# ArduinoProMiniSch.net
KiCad netlist of a schematic drawn in Altium Designer
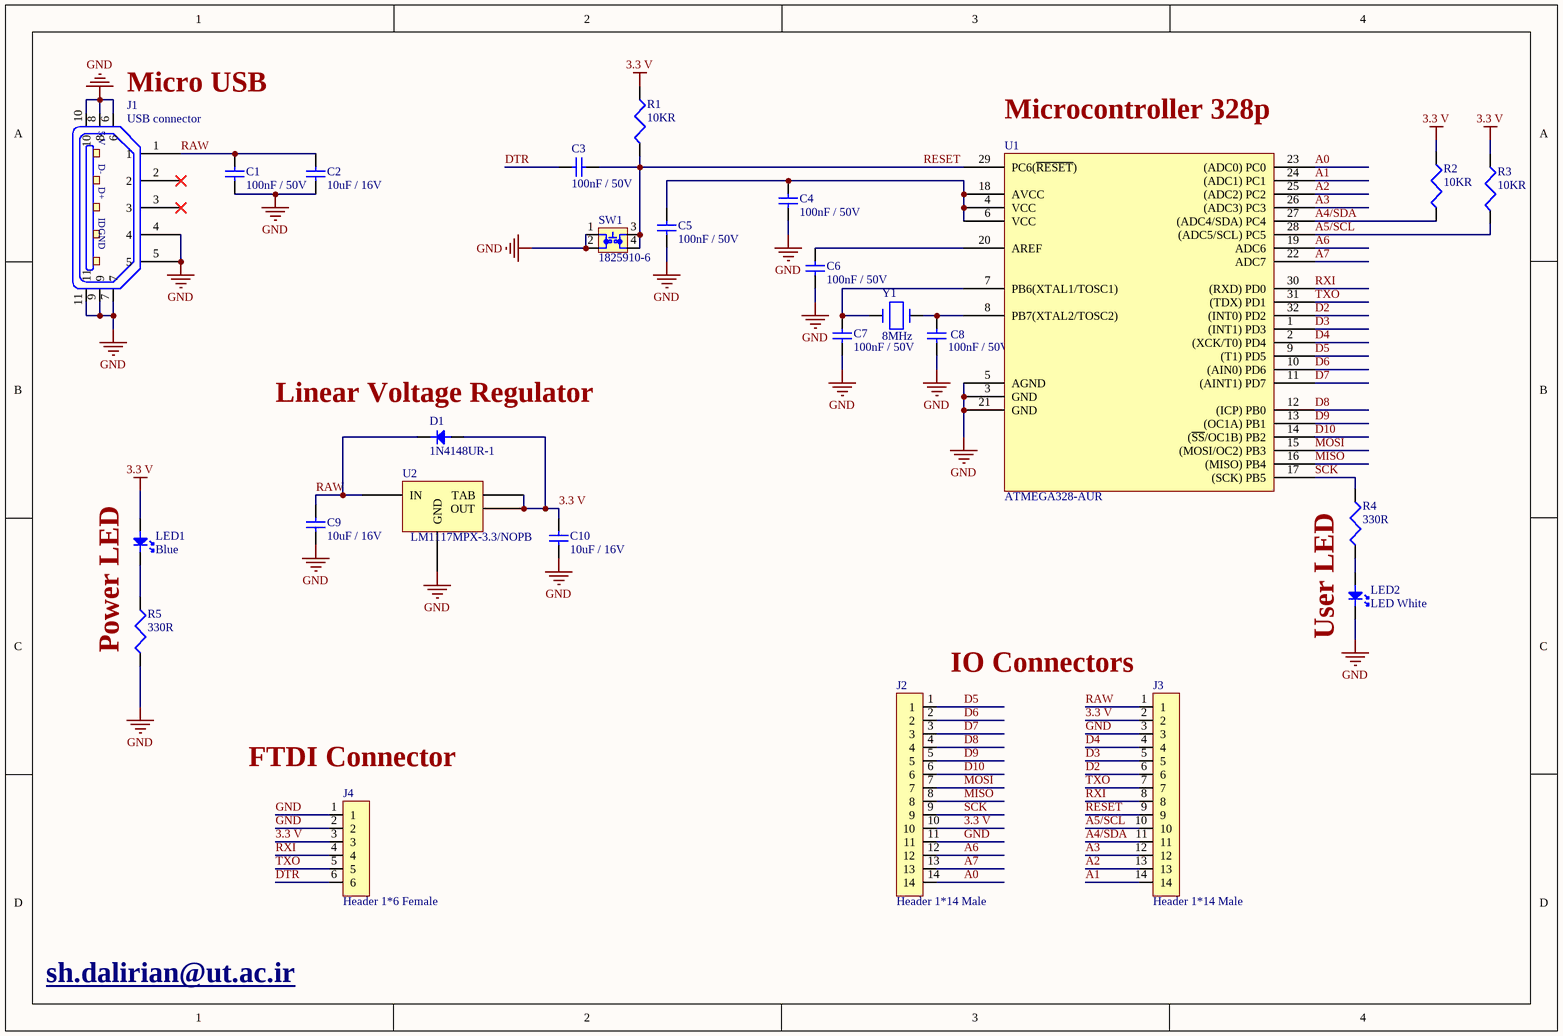
[diagram p0: ArduinoProMiniSch.SchDoc]

(export (version "E")
  (design (tool "Eeschema 10.0.6"))
  (components
    (comp (ref "C1")
      (value "100nF / 50V")
      (footprint "C 0805")
      (description "Capacitor; Ceramic; Cap; .100uF; Tol%; -20%; SMT; Vol-Rtg 50V; Y5V; TR ¦ KEMET C0805C104Z5VACTU")
      (fields
        (field (name "MANUFACTURER") "KEMET")
        (field (name "MANUFACTURER PART NUMBER") "C0805C104Z5VACTU")
      )
      (libsource (lib "ArduinoProMiniSchLib") (part "C0805C104Z5VACTU"))
    )
    (comp (ref "C2")
      (value "10uF / 16V")
      (footprint "C 0805")
      (description "Ceramic capacitor, 10 µF, 16 V (DC), ±10 %, SMD 0805, X5R, C0805C106K4PAC7800")
      (fields
        (field (name "MANUFACTURER") "KEMET")
        (field (name "MANUFACTURER PART NUMBER") "C0805C106K4PACTU")
      )
      (libsource (lib "ArduinoProMiniSchLib") (part "C0805C106K4PACTU"))
    )
    (comp (ref "C3")
      (value "100nF / 50V")
      (footprint "C 0805")
      (description "Capacitor; Ceramic; Cap; .100uF; Tol%; -20%; SMT; Vol-Rtg 50V; Y5V; TR ¦ KEMET C0805C104Z5VACTU")
      (fields
        (field (name "MANUFACTURER") "KEMET")
        (field (name "MANUFACTURER PART NUMBER") "C0805C104Z5VACTU")
      )
      (libsource (lib "ArduinoProMiniSchLib") (part "C0805C104Z5VACTU"))
    )
    (comp (ref "C4")
      (value "100nF / 50V")
      (footprint "C 0805")
      (description "Capacitor; Ceramic; Cap; .100uF; Tol%; -20%; SMT; Vol-Rtg 50V; Y5V; TR ¦ KEMET C0805C104Z5VACTU")
      (fields
        (field (name "MANUFACTURER") "KEMET")
        (field (name "MANUFACTURER PART NUMBER") "C0805C104Z5VACTU")
      )
      (libsource (lib "ArduinoProMiniSchLib") (part "C0805C104Z5VACTU"))
    )
    (comp (ref "C5")
      (value "100nF / 50V")
      (footprint "C 0805")
      (description "Capacitor; Ceramic; Cap; .100uF; Tol%; -20%; SMT; Vol-Rtg 50V; Y5V; TR ¦ KEMET C0805C104Z5VACTU")
      (fields
        (field (name "MANUFACTURER") "KEMET")
        (field (name "MANUFACTURER PART NUMBER") "C0805C104Z5VACTU")
      )
      (libsource (lib "ArduinoProMiniSchLib") (part "C0805C104Z5VACTU"))
    )
    (comp (ref "C6")
      (value "100nF / 50V")
      (footprint "C 0805")
      (description "Capacitor; Ceramic; Cap; .100uF; Tol%; -20%; SMT; Vol-Rtg 50V; Y5V; TR ¦ KEMET C0805C104Z5VACTU")
      (fields
        (field (name "MANUFACTURER") "KEMET")
        (field (name "MANUFACTURER PART NUMBER") "C0805C104Z5VACTU")
      )
      (libsource (lib "ArduinoProMiniSchLib") (part "C0805C104Z5VACTU"))
    )
    (comp (ref "C7")
      (value "100nF / 50V")
      (footprint "C 0805")
      (description "Capacitor; Ceramic; Cap; .100uF; Tol%; -20%; SMT; Vol-Rtg 50V; Y5V; TR ¦ KEMET C0805C104Z5VACTU")
      (fields
        (field (name "MANUFACTURER") "KEMET")
        (field (name "MANUFACTURER PART NUMBER") "C0805C104Z5VACTU")
      )
      (libsource (lib "ArduinoProMiniSchLib") (part "C0805C104Z5VACTU"))
    )
    (comp (ref "C8")
      (value "100nF / 50V")
      (footprint "C 0805")
      (description "Capacitor; Ceramic; Cap; .100uF; Tol%; -20%; SMT; Vol-Rtg 50V; Y5V; TR ¦ KEMET C0805C104Z5VACTU")
      (fields
        (field (name "MANUFACTURER") "KEMET")
        (field (name "MANUFACTURER PART NUMBER") "C0805C104Z5VACTU")
      )
      (libsource (lib "ArduinoProMiniSchLib") (part "C0805C104Z5VACTU"))
    )
    (comp (ref "C9")
      (value "10uF / 16V")
      (footprint "C 0805")
      (description "Ceramic capacitor, 10 µF, 16 V (DC), ±10 %, SMD 0805, X5R, C0805C106K4PAC7800")
      (fields
        (field (name "MANUFACTURER") "KEMET")
        (field (name "MANUFACTURER PART NUMBER") "C0805C106K4PACTU")
      )
      (libsource (lib "ArduinoProMiniSchLib") (part "C0805C106K4PACTU"))
    )
    (comp (ref "C10")
      (value "10uF / 16V")
      (footprint "C 0805")
      (description "Ceramic capacitor, 10 µF, 16 V (DC), ±10 %, SMD 0805, X5R, C0805C106K4PAC7800")
      (fields
        (field (name "MANUFACTURER") "KEMET")
        (field (name "MANUFACTURER PART NUMBER") "C0805C106K4PACTU")
      )
      (libsource (lib "ArduinoProMiniSchLib") (part "C0805C106K4PACTU"))
    )
    (comp (ref "D1")
      (value "1N4148UR-1")
      (footprint "DO-213AA")
      (description "Rectifier Diode Switching 75V 0.2A 5ns 2-Pin DO-213AA Bag")
      (fields (field (name "MANUFACTURER") "Microchip"))
      (libsource (lib "ArduinoProMiniSchLib") (part "1N4148UR-1"))
    )
    (comp (ref "J1")
      (value "USB connector")
      (footprint "USB connector")
      (description "CONN USB MICRO B RECPT SMT R/A")
      (fields
        (field (name "MANUFACTURER") "Amphenol ICC / FCI")
        (field (name "MANUFACTURER PART NUMBER") "10118194-0001LF")
      )
      (libsource (lib "ArduinoProMiniSchLib") (part "10118194-0001LF"))
    )
    (comp (ref "J2")
      (value "Header 1*14 Male")
      (footprint "Header 1*14 Male")
      (description "Conn Unshrouded Header HDR 14 POS 2.54mm Solder ST Thru-Hole Bag")
      (fields
        (field (name "MANUFACTURER") "Adam Equipment")
        (field (name "MANUFACTURER PART NUMBER") "PH1-14-UA")
      )
      (libsource (lib "ArduinoProMiniSchLib") (part "PH1-14-UA"))
    )
    (comp (ref "J3")
      (value "Header 1*14 Male")
      (footprint "Header 1*14 Male")
      (description "Conn Unshrouded Header HDR 14 POS 2.54mm Solder ST Thru-Hole Bag")
      (fields
        (field (name "MANUFACTURER") "Adam Equipment")
        (field (name "MANUFACTURER PART NUMBER") "PH1-14-UA")
      )
      (libsource (lib "") (part "PH1-14-UA_1"))
    )
    (comp (ref "J4")
      (value "Header 1*6 Female")
      (footprint "Header 1*6 Female")
      (description "2.54mm (0.1\") Pitch SIL Vertical PC Tail Socket Assembly, tin, 6 contacts")
      (fields (field (name "MANUFACTURER") "Harwin") (field (name "MANUFACTURER PART NUMBER") "M20-7820646"))
      (libsource (lib "ArduinoProMiniSchLib") (part "M20-7820646"))
    )
    (comp (ref "LED1")
      (value "Blue")
      (footprint "LED 0603")
      (description "LED BLUE CLEAR 0603 SMD")
      (fields
        (field (name "MANUFACTURER") "Vishay Lite-On")
        (field (name "MANUFACTURER PART NUMBER") "LTST-C194TBKT")
      )
      (libsource (lib "ArduinoProMiniSchLib") (part "LTST-C194TBKT"))
    )
    (comp (ref "LED2")
      (value "LED White")
      (footprint "LED 0603")
      (fields (field (name "MANUFACTURER") "Inolux") (field (name "MANUFACTURER PART NUMBER") "IN-S63AT5UW"))
      (libsource (lib "ArduinoProMiniSchLib") (part "IN-S63AT5UW"))
    )
    (comp (ref "R1")
      (value "10KR")
      (footprint "R 0805")
      (description "Res Thick Film 0805 10K Ohm 1% 0.125W(1/8W) +/-100ppm/C Epoxy Pad SMD T/R")
      (fields
        (field (name "MANUFACTURER") "Yageo")
        (field (name "MANUFACTURER PART NUMBER") "RC0805FR-0710KL")
      )
      (libsource (lib "ArduinoProMiniSchLib") (part "RC0805FR-0710KL"))
    )
    (comp (ref "R2")
      (value "10KR")
      (footprint "R 0805")
      (description "Res Thick Film 0805 10K Ohm 1% 0.125W(1/8W) +/-100ppm/C Epoxy Pad SMD T/R")
      (fields
        (field (name "MANUFACTURER") "Yageo")
        (field (name "MANUFACTURER PART NUMBER") "RC0805FR-0710KL")
      )
      (libsource (lib "ArduinoProMiniSchLib") (part "RC0805FR-0710KL"))
    )
    (comp (ref "R3")
      (value "10KR")
      (footprint "R 0805")
      (description "Res Thick Film 0805 10K Ohm 1% 0.125W(1/8W) +/-100ppm/C Epoxy Pad SMD T/R")
      (fields
        (field (name "MANUFACTURER") "Yageo")
        (field (name "MANUFACTURER PART NUMBER") "RC0805FR-0710KL")
      )
      (libsource (lib "ArduinoProMiniSchLib") (part "RC0805FR-0710KL"))
    )
    (comp (ref "R4")
      (value "330R")
      (footprint "R 0805")
      (description "SMD Chip Resistor 330 Ohm ½ 5% 125 Mw 0805 [2012 Metric] Thick Film General Purpose")
      (fields
        (field (name "MANUFACTURER") "Yageo")
        (field (name "MANUFACTURER PART NUMBER") "RC0805JR-07330RL")
      )
      (libsource (lib "ArduinoProMiniSchLib") (part "RC0805JR-07330RL"))
    )
    (comp (ref "R5")
      (value "330R")
      (footprint "R 0805")
      (description "SMD Chip Resistor 330 Ohm ½ 5% 125 Mw 0805 [2012 Metric] Thick Film General Purpose")
      (fields
        (field (name "MANUFACTURER") "Yageo")
        (field (name "MANUFACTURER PART NUMBER") "RC0805JR-07330RL")
      )
      (libsource (lib "ArduinoProMiniSchLib") (part "RC0805JR-07330RL"))
    )
    (comp (ref "SW1")
      (value "1825910-6")
      (footprint "SW-1825910-6")
      (description "Switch Tactile OFF (ON) SPST Round Button PC Pins 0.05A 24VDC 1.57N Thru-Hole Loose")
      (fields (field (name "MANUFACTURER") "TE Connectivity Alcoswitch"))
      (libsource (lib "ArduinoProMiniSchLib") (part "1825910-6"))
    )
    (comp (ref "U1")
      (value "ATMEGA328-AUR")
      (footprint "TQFP32")
      (description "MCU 8-bit ATmega AVR RISC 32KB Flash 2.5V/3.3V/5V 32-Pin TQFP T/R - Tape and Reel")
      (fields (field (name "MANUFACTURER") "Microchip"))
      (libsource (lib "ArduinoProMiniSchLib") (part "ATMEGA328-AUR"))
    )
    (comp (ref "U2")
      (value "LM1117MPX-3.3/NOPB")
      (footprint "SOT223")
      (description "800-mA 15-V linear voltage regulator ; 4-SOT-223 0 to 125")
      (fields (field (name "MANUFACTURER") "Texas Instruments"))
      (libsource (lib "ArduinoProMiniSchLib") (part "LM1117MPX-3.3/NOPB"))
    )
    (comp (ref "Y1")
      (value "8MHz")
      (footprint "CSM-7x")
      (description "Crystal 8MHz ±30ppm (Tol) ±50ppm (Stability) 18pF FUND 60Ohm 2-Pin HC-49/USX SMD T/R")
      (fields
        (field (name "MANUFACTURER") "ECS International")
        (field (name "MANUFACTURER PART NUMBER") "ECS-80-18-5PX-TR")
      )
      (libsource (lib "ArduinoProMiniSchLib") (part "ECS-80-18-5PX-TR"))
    )
  )
  (nets
    (net (code "1") (name "/A0") (class "Default")
      (node (ref "J2") (pin "14") (pinfunction "14_14") (pintype "passive"))
      (node (ref "U1") (pin "23") (pinfunction "(ADC0)_PC0_23") (pintype "passive"))
    )
    (net (code "2") (name "/A1") (class "Default")
      (node (ref "J3") (pin "14") (pinfunction "14_14") (pintype "passive"))
      (node (ref "U1") (pin "24") (pinfunction "(ADC1)_PC1_24") (pintype "passive"))
    )
    (net (code "3") (name "/A2") (class "Default")
      (node (ref "J3") (pin "13") (pinfunction "13_13") (pintype "passive"))
      (node (ref "U1") (pin "25") (pinfunction "(ADC2)_PC2_25") (pintype "passive"))
    )
    (net (code "4") (name "/A3") (class "Default")
      (node (ref "J3") (pin "12") (pinfunction "12_12") (pintype "passive"))
      (node (ref "U1") (pin "26") (pinfunction "(ADC3)_PC3_26") (pintype "passive"))
    )
    (net (code "5") (name "/A4{slash}SDA") (class "Default")
      (node (ref "J3") (pin "11") (pinfunction "11_11") (pintype "passive"))
      (node (ref "R2") (pin "1") (pinfunction "1_1") (pintype "passive"))
      (node (ref "U1") (pin "27") (pinfunction "(ADC4/SDA)_PC4_27") (pintype "passive"))
    )
    (net (code "6") (name "/A5{slash}SCL") (class "Default")
      (node (ref "J3") (pin "10") (pinfunction "10_10") (pintype "passive"))
      (node (ref "R3") (pin "1") (pinfunction "1_1") (pintype "passive"))
      (node (ref "U1") (pin "28") (pinfunction "(ADC5/SCL)_PC5_28") (pintype "passive"))
    )
    (net (code "7") (name "/A6") (class "Default")
      (node (ref "J2") (pin "12") (pinfunction "12_12") (pintype "passive"))
      (node (ref "U1") (pin "19") (pinfunction "ADC6_19") (pintype "passive"))
    )
    (net (code "8") (name "/A7") (class "Default")
      (node (ref "J2") (pin "13") (pinfunction "13_13") (pintype "passive"))
      (node (ref "U1") (pin "22") (pinfunction "ADC7_22") (pintype "passive"))
    )
    (net (code "9") (name "/D2") (class "Default")
      (node (ref "J3") (pin "6") (pinfunction "6_6") (pintype "passive"))
      (node (ref "U1") (pin "32") (pinfunction "(INT0)_PD2_32") (pintype "passive"))
    )
    (net (code "10") (name "/D3") (class "Default")
      (node (ref "J3") (pin "5") (pinfunction "5_5") (pintype "passive"))
      (node (ref "U1") (pin "1") (pinfunction "(INT1)_PD3_1") (pintype "passive"))
    )
    (net (code "11") (name "/D4") (class "Default")
      (node (ref "J3") (pin "4") (pinfunction "4_4") (pintype "passive"))
      (node (ref "U1") (pin "2") (pinfunction "(XCK/T0)_PD4_2") (pintype "passive"))
    )
    (net (code "12") (name "/D5") (class "Default")
      (node (ref "J2") (pin "1") (pinfunction "1_1") (pintype "passive"))
      (node (ref "U1") (pin "9") (pinfunction "(T1)_PD5_9") (pintype "passive"))
    )
    (net (code "13") (name "/D6") (class "Default")
      (node (ref "J2") (pin "2") (pinfunction "2_2") (pintype "passive"))
      (node (ref "U1") (pin "10") (pinfunction "(AIN0)_PD6_10") (pintype "passive"))
    )
    (net (code "14") (name "/D7") (class "Default")
      (node (ref "J2") (pin "3") (pinfunction "3_3") (pintype "passive"))
      (node (ref "U1") (pin "11") (pinfunction "(AINT1)_PD7_11") (pintype "passive"))
    )
    (net (code "15") (name "/D8") (class "Default")
      (node (ref "J2") (pin "4") (pinfunction "4_4") (pintype "passive"))
      (node (ref "U1") (pin "12") (pinfunction "(ICP)_PB0_12") (pintype "passive"))
    )
    (net (code "16") (name "/D9") (class "Default")
      (node (ref "J2") (pin "5") (pinfunction "5_5") (pintype "passive"))
      (node (ref "U1") (pin "13") (pinfunction "(OC1A)_PB1_13") (pintype "passive"))
    )
    (net (code "17") (name "/D10") (class "Default")
      (node (ref "J2") (pin "6") (pinfunction "6_6") (pintype "passive"))
      (node (ref "U1") (pin "14") (pinfunction "(~{SS}/OC1B)_PB2_14") (pintype "passive"))
    )
    (net (code "18") (name "/DTR") (class "Default")
      (node (ref "C3") (pin "1") (pinfunction "1_1") (pintype "passive"))
      (node (ref "J4") (pin "6") (pinfunction "6_6") (pintype "passive"))
    )
    (net (code "19") (name "/MISO") (class "Default")
      (node (ref "J2") (pin "8") (pinfunction "8_8") (pintype "passive"))
      (node (ref "U1") (pin "16") (pinfunction "(MISO)_PB4_16") (pintype "passive"))
    )
    (net (code "20") (name "/MOSI") (class "Default")
      (node (ref "J2") (pin "7") (pinfunction "7_7") (pintype "passive"))
      (node (ref "U1") (pin "15") (pinfunction "(MOSI/OC2)_PB3_15") (pintype "passive"))
    )
    (net (code "21") (name "/RAW") (class "Default")
      (node (ref "C1") (pin "2") (pinfunction "2_2") (pintype "passive"))
      (node (ref "C2") (pin "2") (pinfunction "2_2") (pintype "passive"))
      (node (ref "C9") (pin "2") (pinfunction "2_2") (pintype "passive"))
      (node (ref "D1") (pin "2") (pinfunction "Cathode_2") (pintype "passive"))
      (node (ref "J1") (pin "1") (pinfunction "1_1") (pintype "passive"))
      (node (ref "J3") (pin "1") (pinfunction "1_1") (pintype "passive"))
      (node (ref "U2") (pin "4") (pinfunction "IN_4") (pintype "passive"))
    )
    (net (code "22") (name "/RESET") (class "Default")
      (node (ref "C3") (pin "2") (pinfunction "2_2") (pintype "passive"))
      (node (ref "J3") (pin "9") (pinfunction "9_9") (pintype "passive"))
      (node (ref "R1") (pin "1") (pinfunction "1_1") (pintype "passive"))
      (node (ref "SW1") (pin "3") (pinfunction "3_3") (pintype "passive"))
      (node (ref "SW1") (pin "4") (pinfunction "4_4") (pintype "passive"))
      (node (ref "U1") (pin "29") (pinfunction "PC6(~{RESET})_29") (pintype "passive"))
    )
    (net (code "23") (name "/RXI") (class "Default")
      (node (ref "J3") (pin "8") (pinfunction "8_8") (pintype "passive"))
      (node (ref "J4") (pin "4") (pinfunction "4_4") (pintype "passive"))
      (node (ref "U1") (pin "30") (pinfunction "(RXD)_PD0_30") (pintype "passive"))
    )
    (net (code "24") (name "/SCK") (class "Default")
      (node (ref "J2") (pin "9") (pinfunction "9_9") (pintype "passive"))
      (node (ref "R4") (pin "2") (pinfunction "2_2") (pintype "passive"))
      (node (ref "U1") (pin "17") (pinfunction "(SCK)_PB5_17") (pintype "passive"))
    )
    (net (code "25") (name "/TXO") (class "Default")
      (node (ref "J3") (pin "7") (pinfunction "7_7") (pintype "passive"))
      (node (ref "J4") (pin "5") (pinfunction "5_5") (pintype "passive"))
      (node (ref "U1") (pin "31") (pinfunction "(TDX)_PD1_31") (pintype "passive"))
    )
    (net (code "26") (name "3.3 V") (class "Default")
      (node (ref "C10") (pin "2") (pinfunction "2_2") (pintype "passive"))
      (node (ref "D1") (pin "1") (pinfunction "Anode_1") (pintype "passive"))
      (node (ref "J2") (pin "10") (pinfunction "10_10") (pintype "passive"))
      (node (ref "J3") (pin "2") (pinfunction "2_2") (pintype "passive"))
      (node (ref "J4") (pin "3") (pinfunction "3_3") (pintype "passive"))
      (node (ref "LED1") (pin "1") (pinfunction "Anode_1") (pintype "passive"))
      (node (ref "R1") (pin "2") (pinfunction "2_2") (pintype "passive"))
      (node (ref "R2") (pin "2") (pinfunction "2_2") (pintype "passive"))
      (node (ref "R3") (pin "2") (pinfunction "2_2") (pintype "passive"))
      (node (ref "U2") (pin "2") (pinfunction "OUT_2") (pintype "passive"))
      (node (ref "U2") (pin "3") (pinfunction "TAB_3") (pintype "passive"))
    )
    (net (code "27") (name "GND") (class "Default")
      (node (ref "C1") (pin "1") (pinfunction "1_1") (pintype "passive"))
      (node (ref "C10") (pin "1") (pinfunction "1_1") (pintype "passive"))
      (node (ref "C2") (pin "1") (pinfunction "1_1") (pintype "passive"))
      (node (ref "C4") (pin "1") (pinfunction "1_1") (pintype "passive"))
      (node (ref "C5") (pin "1") (pinfunction "1_1") (pintype "passive"))
      (node (ref "C6") (pin "1") (pinfunction "1_1") (pintype "passive"))
      (node (ref "C7") (pin "1") (pinfunction "1_1") (pintype "passive"))
      (node (ref "C8") (pin "1") (pinfunction "1_1") (pintype "passive"))
      (node (ref "C9") (pin "1") (pinfunction "1_1") (pintype "passive"))
      (node (ref "J1") (pin "10") (pinfunction "10_10") (pintype "passive"))
      (node (ref "J1") (pin "11") (pinfunction "11_11") (pintype "passive"))
      (node (ref "J1") (pin "4") (pinfunction "4_4") (pintype "passive"))
      (node (ref "J1") (pin "5") (pinfunction "5_5") (pintype "passive"))
      (node (ref "J1") (pin "6") (pinfunction "6_6") (pintype "passive"))
      (node (ref "J1") (pin "7") (pinfunction "7_7") (pintype "passive"))
      (node (ref "J1") (pin "8") (pinfunction "8_8") (pintype "passive"))
      (node (ref "J1") (pin "9") (pinfunction "9_9") (pintype "passive"))
      (node (ref "J2") (pin "11") (pinfunction "11_11") (pintype "passive"))
      (node (ref "J3") (pin "3") (pinfunction "3_3") (pintype "passive"))
      (node (ref "J4") (pin "1") (pinfunction "1_1") (pintype "passive"))
      (node (ref "J4") (pin "2") (pinfunction "2_2") (pintype "passive"))
      (node (ref "LED2") (pin "2") (pinfunction "Cathode_2") (pintype "passive"))
      (node (ref "R5") (pin "1") (pinfunction "1_1") (pintype "passive"))
      (node (ref "SW1") (pin "1") (pinfunction "3_1") (pintype "passive"))
      (node (ref "SW1") (pin "2") (pinfunction "2_2") (pintype "passive"))
      (node (ref "U1") (pin "21") (pinfunction "GND_21") (pintype "passive"))
      (node (ref "U1") (pin "3") (pinfunction "GND_3") (pintype "passive"))
      (node (ref "U1") (pin "5") (pinfunction "AGND_5") (pintype "passive"))
      (node (ref "U2") (pin "1") (pinfunction "GND_1") (pintype "passive"))
    )
    (net (code "28") (name "Net-(LED1-Cathode)") (class "Default")
      (node (ref "LED1") (pin "2") (pinfunction "Cathode_2") (pintype "passive"))
      (node (ref "R5") (pin "2") (pinfunction "2_2") (pintype "passive"))
    )
    (net (code "29") (name "Net-(LED2-Anode)") (class "Default")
      (node (ref "LED2") (pin "1") (pinfunction "Anode_1") (pintype "passive"))
      (node (ref "R4") (pin "1") (pinfunction "1_1") (pintype "passive"))
    )
    (net (code "30") (name "Net-(U1-AREF)") (class "Default")
      (node (ref "C6") (pin "2") (pinfunction "2_2") (pintype "passive"))
      (node (ref "U1") (pin "20") (pinfunction "AREF_20") (pintype "passive"))
    )
    (net (code "31") (name "Net-(U1-AVCC)") (class "Default")
      (node (ref "C4") (pin "2") (pinfunction "2_2") (pintype "passive"))
      (node (ref "C5") (pin "2") (pinfunction "2_2") (pintype "passive"))
      (node (ref "U1") (pin "18") (pinfunction "AVCC_18") (pintype "passive"))
      (node (ref "U1") (pin "4") (pinfunction "VCC_4") (pintype "passive"))
      (node (ref "U1") (pin "6") (pinfunction "VCC_6") (pintype "passive"))
    )
    (net (code "32") (name "Net-(U1-PB6(XTAL1{slash}TOSC1))") (class "Default")
      (node (ref "C7") (pin "2") (pinfunction "2_2") (pintype "passive"))
      (node (ref "U1") (pin "7") (pinfunction "PB6(XTAL1/TOSC1)_7") (pintype "passive"))
      (node (ref "Y1") (pin "1") (pinfunction "1_1") (pintype "passive"))
    )
    (net (code "33") (name "Net-(U1-PB7(XTAL2{slash}TOSC2))") (class "Default")
      (node (ref "C8") (pin "2") (pinfunction "2_2") (pintype "passive"))
      (node (ref "U1") (pin "8") (pinfunction "PB7(XTAL2/TOSC2)_8") (pintype "passive"))
      (node (ref "Y1") (pin "2") (pinfunction "2_2") (pintype "passive"))
    )
    (net (code "34") (name "unconnected-(J1-Pad2)") (class "Default")
      (node (ref "J1") (pin "2") (pinfunction "2_2") (pintype "passive+no_connect"))
    )
    (net (code "35") (name "unconnected-(J1-Pad3)") (class "Default")
      (node (ref "J1") (pin "3") (pinfunction "3_3") (pintype "passive+no_connect"))
    )
  )
)
